# exp21dc.net
KiCad netlist of a schematic drawn in EAGLE
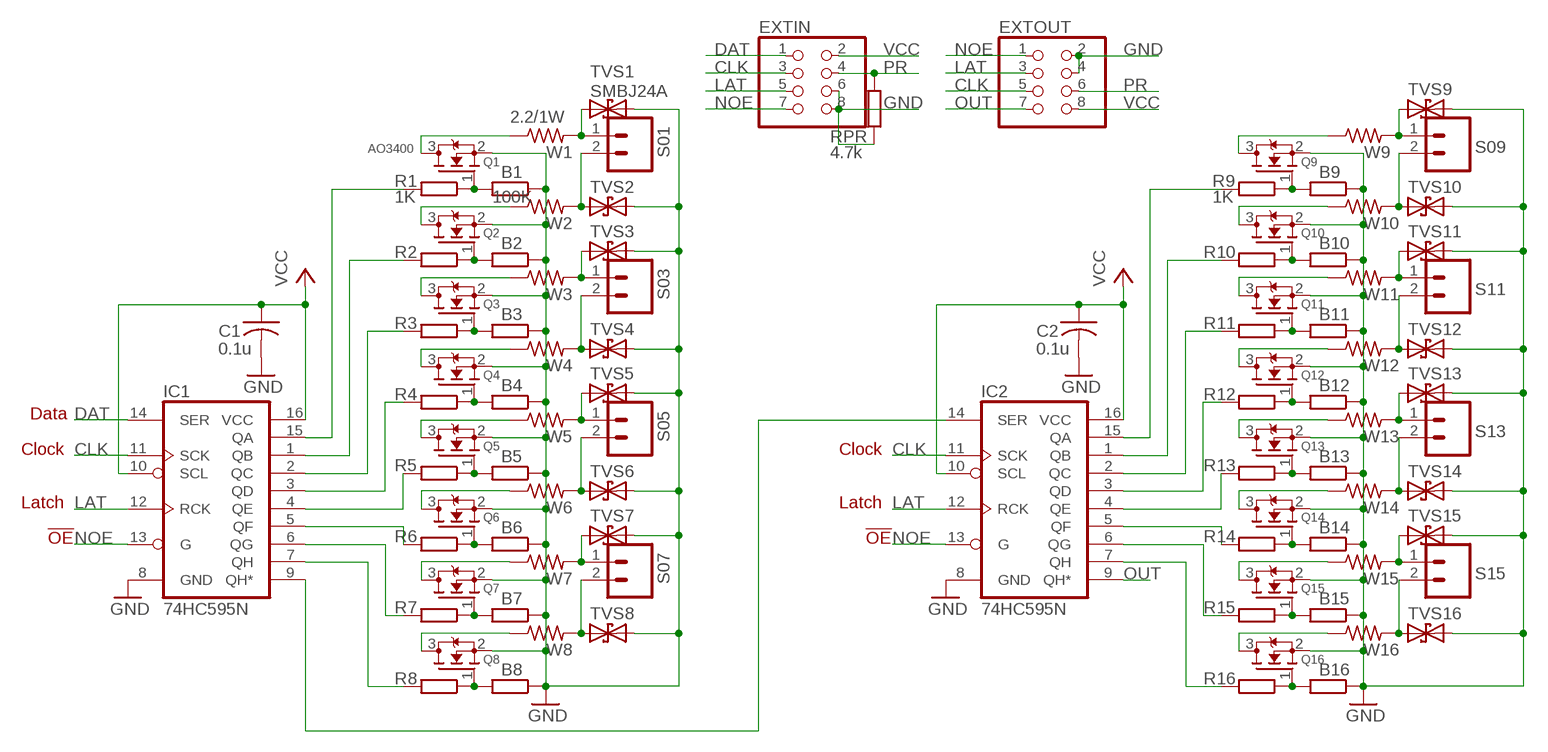
[diagram p0: schematic, sheet 1]

(export (version "E")
  (design (tool "Eeschema 10.0.6"))
  (components
    (comp (ref "B1")
      (value "100K")
      (footprint "eagle-import:R0603")
      (libsource (lib "eagle-import") (part "R-EU_R0603"))
    )
    (comp (ref "B2")
      (value "100K")
      (footprint "eagle-import:R0603")
      (libsource (lib "eagle-import") (part "R-EU_R0603"))
    )
    (comp (ref "B3")
      (value "100K")
      (footprint "eagle-import:R0603")
      (libsource (lib "eagle-import") (part "R-EU_R0603"))
    )
    (comp (ref "B4")
      (value "100K")
      (footprint "eagle-import:R0603")
      (libsource (lib "eagle-import") (part "R-EU_R0603"))
    )
    (comp (ref "B5")
      (value "100K")
      (footprint "eagle-import:R0603")
      (libsource (lib "eagle-import") (part "R-EU_R0603"))
    )
    (comp (ref "B6")
      (value "100K")
      (footprint "eagle-import:R0603")
      (libsource (lib "eagle-import") (part "R-EU_R0603"))
    )
    (comp (ref "B7")
      (value "100K")
      (footprint "eagle-import:R0603")
      (libsource (lib "eagle-import") (part "R-EU_R0603"))
    )
    (comp (ref "B8")
      (value "100K")
      (footprint "eagle-import:R0603")
      (libsource (lib "eagle-import") (part "R-EU_R0603"))
    )
    (comp (ref "B9")
      (value "100K")
      (footprint "eagle-import:R0603")
      (libsource (lib "eagle-import") (part "R-EU_R0603"))
    )
    (comp (ref "B10")
      (value "100K")
      (footprint "eagle-import:R0603")
      (libsource (lib "eagle-import") (part "R-EU_R0603"))
    )
    (comp (ref "B11")
      (value "100K")
      (footprint "eagle-import:R0603")
      (libsource (lib "eagle-import") (part "R-EU_R0603"))
    )
    (comp (ref "B12")
      (value "100K")
      (footprint "eagle-import:R0603")
      (libsource (lib "eagle-import") (part "R-EU_R0603"))
    )
    (comp (ref "B13")
      (value "100K")
      (footprint "eagle-import:R0603")
      (libsource (lib "eagle-import") (part "R-EU_R0603"))
    )
    (comp (ref "B14")
      (value "100K")
      (footprint "eagle-import:R0603")
      (libsource (lib "eagle-import") (part "R-EU_R0603"))
    )
    (comp (ref "B15")
      (value "100K")
      (footprint "eagle-import:R0603")
      (libsource (lib "eagle-import") (part "R-EU_R0603"))
    )
    (comp (ref "B16")
      (value "100K")
      (footprint "eagle-import:R0603")
      (libsource (lib "eagle-import") (part "R-EU_R0603"))
    )
    (comp (ref "C1")
      (value "0.1u")
      (footprint "eagle-import:C0603K")
      (libsource (lib "eagle-import") (part "C-USC0603K"))
    )
    (comp (ref "C2")
      (value "0.1u")
      (footprint "eagle-import:C0603K")
      (libsource (lib "eagle-import") (part "C-USC0603K"))
    )
    (comp (ref "EXTIN")
      (value "PINHD-2X4/90")
      (footprint "eagle-import:2X04_90")
      (libsource (lib "eagle-import") (part "PINHD-2X4/90"))
    )
    (comp (ref "EXTOUT")
      (value "PINHD-2X4/90")
      (footprint "eagle-import:2X04_90")
      (libsource (lib "eagle-import") (part "PINHD-2X4/90"))
    )
    (comp (ref "IC1")
      (value "74HC595N")
      (footprint "eagle-import:SO16")
      (libsource (lib "eagle-import") (part "74595DLS"))
    )
    (comp (ref "IC2")
      (value "74HC595N")
      (footprint "eagle-import:SO16")
      (libsource (lib "eagle-import") (part "74595DLS"))
    )
    (comp (ref "Q1")
      (value "AO3400")
      (footprint "eagle-import:SOT23")
      (libsource (lib "eagle-import") (part "MOSFET-NREFLOW"))
    )
    (comp (ref "Q2")
      (value "MOSFET-NREFLOW")
      (footprint "eagle-import:SOT23")
      (libsource (lib "eagle-import") (part "MOSFET-NREFLOW"))
    )
    (comp (ref "Q3")
      (value "MOSFET-NREFLOW")
      (footprint "eagle-import:SOT23")
      (libsource (lib "eagle-import") (part "MOSFET-NREFLOW"))
    )
    (comp (ref "Q4")
      (value "MOSFET-NREFLOW")
      (footprint "eagle-import:SOT23")
      (libsource (lib "eagle-import") (part "MOSFET-NREFLOW"))
    )
    (comp (ref "Q5")
      (value "MOSFET-NREFLOW")
      (footprint "eagle-import:SOT23")
      (libsource (lib "eagle-import") (part "MOSFET-NREFLOW"))
    )
    (comp (ref "Q6")
      (value "MOSFET-NREFLOW")
      (footprint "eagle-import:SOT23")
      (libsource (lib "eagle-import") (part "MOSFET-NREFLOW"))
    )
    (comp (ref "Q7")
      (value "MOSFET-NREFLOW")
      (footprint "eagle-import:SOT23")
      (libsource (lib "eagle-import") (part "MOSFET-NREFLOW"))
    )
    (comp (ref "Q8")
      (value "MOSFET-NREFLOW")
      (footprint "eagle-import:SOT23")
      (libsource (lib "eagle-import") (part "MOSFET-NREFLOW"))
    )
    (comp (ref "Q9")
      (value "MOSFET-NREFLOW")
      (footprint "eagle-import:SOT23")
      (libsource (lib "eagle-import") (part "MOSFET-NREFLOW"))
    )
    (comp (ref "Q10")
      (value "MOSFET-NREFLOW")
      (footprint "eagle-import:SOT23")
      (libsource (lib "eagle-import") (part "MOSFET-NREFLOW"))
    )
    (comp (ref "Q11")
      (value "MOSFET-NREFLOW")
      (footprint "eagle-import:SOT23")
      (libsource (lib "eagle-import") (part "MOSFET-NREFLOW"))
    )
    (comp (ref "Q12")
      (value "MOSFET-NREFLOW")
      (footprint "eagle-import:SOT23")
      (libsource (lib "eagle-import") (part "MOSFET-NREFLOW"))
    )
    (comp (ref "Q13")
      (value "MOSFET-NREFLOW")
      (footprint "eagle-import:SOT23")
      (libsource (lib "eagle-import") (part "MOSFET-NREFLOW"))
    )
    (comp (ref "Q14")
      (value "MOSFET-NREFLOW")
      (footprint "eagle-import:SOT23")
      (libsource (lib "eagle-import") (part "MOSFET-NREFLOW"))
    )
    (comp (ref "Q15")
      (value "MOSFET-NREFLOW")
      (footprint "eagle-import:SOT23")
      (libsource (lib "eagle-import") (part "MOSFET-NREFLOW"))
    )
    (comp (ref "Q16")
      (value "MOSFET-NREFLOW")
      (footprint "eagle-import:SOT23")
      (libsource (lib "eagle-import") (part "MOSFET-NREFLOW"))
    )
    (comp (ref "R1")
      (value "1K")
      (footprint "eagle-import:R0603")
      (libsource (lib "eagle-import") (part "R-EU_R0603"))
    )
    (comp (ref "R2")
      (value "1K")
      (footprint "eagle-import:R0603")
      (libsource (lib "eagle-import") (part "R-EU_R0603"))
    )
    (comp (ref "R3")
      (value "1K")
      (footprint "eagle-import:R0603")
      (libsource (lib "eagle-import") (part "R-EU_R0603"))
    )
    (comp (ref "R4")
      (value "1K")
      (footprint "eagle-import:R0603")
      (libsource (lib "eagle-import") (part "R-EU_R0603"))
    )
    (comp (ref "R5")
      (value "1K")
      (footprint "eagle-import:R0603")
      (libsource (lib "eagle-import") (part "R-EU_R0603"))
    )
    (comp (ref "R6")
      (value "1K")
      (footprint "eagle-import:R0603")
      (libsource (lib "eagle-import") (part "R-EU_R0603"))
    )
    (comp (ref "R7")
      (value "1K")
      (footprint "eagle-import:R0603")
      (libsource (lib "eagle-import") (part "R-EU_R0603"))
    )
    (comp (ref "R8")
      (value "1K")
      (footprint "eagle-import:R0603")
      (libsource (lib "eagle-import") (part "R-EU_R0603"))
    )
    (comp (ref "R9")
      (value "1K")
      (footprint "eagle-import:R0603")
      (libsource (lib "eagle-import") (part "R-EU_R0603"))
    )
    (comp (ref "R10")
      (value "1K")
      (footprint "eagle-import:R0603")
      (libsource (lib "eagle-import") (part "R-EU_R0603"))
    )
    (comp (ref "R11")
      (value "1K")
      (footprint "eagle-import:R0603")
      (libsource (lib "eagle-import") (part "R-EU_R0603"))
    )
    (comp (ref "R12")
      (value "1K")
      (footprint "eagle-import:R0603")
      (libsource (lib "eagle-import") (part "R-EU_R0603"))
    )
    (comp (ref "R13")
      (value "1K")
      (footprint "eagle-import:R0603")
      (libsource (lib "eagle-import") (part "R-EU_R0603"))
    )
    (comp (ref "R14")
      (value "1K")
      (footprint "eagle-import:R0603")
      (libsource (lib "eagle-import") (part "R-EU_R0603"))
    )
    (comp (ref "R15")
      (value "1K")
      (footprint "eagle-import:R0603")
      (libsource (lib "eagle-import") (part "R-EU_R0603"))
    )
    (comp (ref "R16")
      (value "1K")
      (footprint "eagle-import:R0603")
      (libsource (lib "eagle-import") (part "R-EU_R0603"))
    )
    (comp (ref "RPR")
      (value "4.7k")
      (footprint "eagle-import:R0603")
      (libsource (lib "eagle-import") (part "R-EU_R0603"))
    )
    (comp (ref "S01")
      (value "M025MM-X")
      (footprint "eagle-import:SCREWTERMINAL-5MM-2-X")
      (libsource (lib "eagle-import") (part "M025MM-X"))
    )
    (comp (ref "S03")
      (value "M025MM-X")
      (footprint "eagle-import:SCREWTERMINAL-5MM-2-X")
      (libsource (lib "eagle-import") (part "M025MM-X"))
    )
    (comp (ref "S05")
      (value "M025MM-X")
      (footprint "eagle-import:SCREWTERMINAL-5MM-2-X")
      (libsource (lib "eagle-import") (part "M025MM-X"))
    )
    (comp (ref "S07")
      (value "M025MM-X")
      (footprint "eagle-import:SCREWTERMINAL-5MM-2-X")
      (libsource (lib "eagle-import") (part "M025MM-X"))
    )
    (comp (ref "S09")
      (value "M025MM-X")
      (footprint "eagle-import:SCREWTERMINAL-5MM-2-X")
      (libsource (lib "eagle-import") (part "M025MM-X"))
    )
    (comp (ref "S11")
      (value "M025MM-X")
      (footprint "eagle-import:SCREWTERMINAL-5MM-2-X")
      (libsource (lib "eagle-import") (part "M025MM-X"))
    )
    (comp (ref "S13")
      (value "M025MM-X")
      (footprint "eagle-import:SCREWTERMINAL-5MM-2-X")
      (libsource (lib "eagle-import") (part "M025MM-X"))
    )
    (comp (ref "S15")
      (value "M025MM-X")
      (footprint "eagle-import:SCREWTERMINAL-5MM-2-X")
      (libsource (lib "eagle-import") (part "M025MM-X"))
    )
    (comp (ref "TVS1")
      (value "SMBJ24A")
      (footprint "eagle-import:SMB")
      (libsource (lib "eagle-import") (part "TVSSMB"))
    )
    (comp (ref "TVS2")
      (value "TVSSMB")
      (footprint "eagle-import:SMB")
      (libsource (lib "eagle-import") (part "TVSSMB"))
    )
    (comp (ref "TVS3")
      (value "TVSSMB")
      (footprint "eagle-import:SMB")
      (libsource (lib "eagle-import") (part "TVSSMB"))
    )
    (comp (ref "TVS4")
      (value "TVSSMB")
      (footprint "eagle-import:SMB")
      (libsource (lib "eagle-import") (part "TVSSMB"))
    )
    (comp (ref "TVS5")
      (value "TVSSMB")
      (footprint "eagle-import:SMB")
      (libsource (lib "eagle-import") (part "TVSSMB"))
    )
    (comp (ref "TVS6")
      (value "TVSSMB")
      (footprint "eagle-import:SMB")
      (libsource (lib "eagle-import") (part "TVSSMB"))
    )
    (comp (ref "TVS7")
      (value "TVSSMB")
      (footprint "eagle-import:SMB")
      (libsource (lib "eagle-import") (part "TVSSMB"))
    )
    (comp (ref "TVS8")
      (value "TVSSMB")
      (footprint "eagle-import:SMB")
      (libsource (lib "eagle-import") (part "TVSSMB"))
    )
    (comp (ref "TVS9")
      (value "TVSSMB")
      (footprint "eagle-import:SMB")
      (libsource (lib "eagle-import") (part "TVSSMB"))
    )
    (comp (ref "TVS10")
      (value "TVSSMB")
      (footprint "eagle-import:SMB")
      (libsource (lib "eagle-import") (part "TVSSMB"))
    )
    (comp (ref "TVS11")
      (value "TVSSMB")
      (footprint "eagle-import:SMB")
      (libsource (lib "eagle-import") (part "TVSSMB"))
    )
    (comp (ref "TVS12")
      (value "TVSSMB")
      (footprint "eagle-import:SMB")
      (libsource (lib "eagle-import") (part "TVSSMB"))
    )
    (comp (ref "TVS13")
      (value "TVSSMB")
      (footprint "eagle-import:SMB")
      (libsource (lib "eagle-import") (part "TVSSMB"))
    )
    (comp (ref "TVS14")
      (value "TVSSMB")
      (footprint "eagle-import:SMB")
      (libsource (lib "eagle-import") (part "TVSSMB"))
    )
    (comp (ref "TVS15")
      (value "TVSSMB")
      (footprint "eagle-import:SMB")
      (libsource (lib "eagle-import") (part "TVSSMB"))
    )
    (comp (ref "TVS16")
      (value "TVSSMB")
      (footprint "eagle-import:SMB")
      (libsource (lib "eagle-import") (part "TVSSMB"))
    )
    (comp (ref "W1")
      (value "2.2/1W")
      (footprint "eagle-import:R2512")
      (libsource (lib "eagle-import") (part "R-US_R2512"))
    )
    (comp (ref "W2")
      (value "R-US_R2512")
      (footprint "eagle-import:R2512")
      (libsource (lib "eagle-import") (part "R-US_R2512"))
    )
    (comp (ref "W3")
      (value "R-US_R2512")
      (footprint "eagle-import:R2512")
      (libsource (lib "eagle-import") (part "R-US_R2512"))
    )
    (comp (ref "W4")
      (value "R-US_R2512")
      (footprint "eagle-import:R2512")
      (libsource (lib "eagle-import") (part "R-US_R2512"))
    )
    (comp (ref "W5")
      (value "R-US_R2512")
      (footprint "eagle-import:R2512")
      (libsource (lib "eagle-import") (part "R-US_R2512"))
    )
    (comp (ref "W6")
      (value "R-US_R2512")
      (footprint "eagle-import:R2512")
      (libsource (lib "eagle-import") (part "R-US_R2512"))
    )
    (comp (ref "W7")
      (value "R-US_R2512")
      (footprint "eagle-import:R2512")
      (libsource (lib "eagle-import") (part "R-US_R2512"))
    )
    (comp (ref "W8")
      (value "R-US_R2512")
      (footprint "eagle-import:R2512")
      (libsource (lib "eagle-import") (part "R-US_R2512"))
    )
    (comp (ref "W9")
      (value "R-US_R2512")
      (footprint "eagle-import:R2512")
      (libsource (lib "eagle-import") (part "R-US_R2512"))
    )
    (comp (ref "W10")
      (value "R-US_R2512")
      (footprint "eagle-import:R2512")
      (libsource (lib "eagle-import") (part "R-US_R2512"))
    )
    (comp (ref "W11")
      (value "R-US_R2512")
      (footprint "eagle-import:R2512")
      (libsource (lib "eagle-import") (part "R-US_R2512"))
    )
    (comp (ref "W12")
      (value "R-US_R2512")
      (footprint "eagle-import:R2512")
      (libsource (lib "eagle-import") (part "R-US_R2512"))
    )
    (comp (ref "W13")
      (value "R-US_R2512")
      (footprint "eagle-import:R2512")
      (libsource (lib "eagle-import") (part "R-US_R2512"))
    )
    (comp (ref "W14")
      (value "R-US_R2512")
      (footprint "eagle-import:R2512")
      (libsource (lib "eagle-import") (part "R-US_R2512"))
    )
    (comp (ref "W15")
      (value "R-US_R2512")
      (footprint "eagle-import:R2512")
      (libsource (lib "eagle-import") (part "R-US_R2512"))
    )
    (comp (ref "W16")
      (value "R-US_R2512")
      (footprint "eagle-import:R2512")
      (libsource (lib "eagle-import") (part "R-US_R2512"))
    )
  )
  (nets
    (net (code "1") (name "/CLK") (class "Default")
      (node (ref "EXTIN") (pin "3") (pinfunction "3_3") (pintype "passive"))
      (node (ref "EXTOUT") (pin "5") (pinfunction "5_5") (pintype "passive"))
      (node (ref "IC1") (pin "11") (pinfunction "SCK_11") (pintype "input"))
      (node (ref "IC2") (pin "11") (pinfunction "SCK_11") (pintype "input"))
    )
    (net (code "2") (name "/DAT") (class "Default")
      (node (ref "EXTIN") (pin "1") (pinfunction "1_1") (pintype "passive"))
      (node (ref "IC1") (pin "14") (pinfunction "SER_14") (pintype "input"))
    )
    (net (code "3") (name "/LAT") (class "Default")
      (node (ref "EXTIN") (pin "5") (pinfunction "5_5") (pintype "passive"))
      (node (ref "EXTOUT") (pin "3") (pinfunction "3_3") (pintype "passive"))
      (node (ref "IC1") (pin "12") (pinfunction "RCK_12") (pintype "input"))
      (node (ref "IC2") (pin "12") (pinfunction "RCK_12") (pintype "input"))
    )
    (net (code "4") (name "/NOE") (class "Default")
      (node (ref "EXTIN") (pin "7") (pinfunction "7_7") (pintype "passive"))
      (node (ref "EXTOUT") (pin "1") (pinfunction "1_1") (pintype "passive"))
      (node (ref "IC1") (pin "13") (pinfunction "G_13") (pintype "input"))
      (node (ref "IC2") (pin "13") (pinfunction "G_13") (pintype "input"))
    )
    (net (code "5") (name "/OUT") (class "Default")
      (node (ref "EXTOUT") (pin "7") (pinfunction "7_7") (pintype "passive"))
      (node (ref "IC2") (pin "9") (pinfunction "QH*_9") (pintype "tri_state"))
    )
    (net (code "6") (name "/PR") (class "Default")
      (node (ref "EXTIN") (pin "4") (pinfunction "4_4") (pintype "passive"))
      (node (ref "EXTOUT") (pin "6") (pinfunction "6_6") (pintype "passive"))
      (node (ref "RPR") (pin "2") (pinfunction "2_2") (pintype "passive"))
    )
    (net (code "7") (name "GND") (class "Default")
      (node (ref "B1") (pin "1") (pinfunction "1_1") (pintype "passive"))
      (node (ref "B10") (pin "1") (pinfunction "1_1") (pintype "passive"))
      (node (ref "B11") (pin "1") (pinfunction "1_1") (pintype "passive"))
      (node (ref "B12") (pin "1") (pinfunction "1_1") (pintype "passive"))
      (node (ref "B13") (pin "1") (pinfunction "1_1") (pintype "passive"))
      (node (ref "B14") (pin "1") (pinfunction "1_1") (pintype "passive"))
      (node (ref "B15") (pin "1") (pinfunction "1_1") (pintype "passive"))
      (node (ref "B16") (pin "1") (pinfunction "1_1") (pintype "passive"))
      (node (ref "B2") (pin "1") (pinfunction "1_1") (pintype "passive"))
      (node (ref "B3") (pin "1") (pinfunction "1_1") (pintype "passive"))
      (node (ref "B4") (pin "1") (pinfunction "1_1") (pintype "passive"))
      (node (ref "B5") (pin "1") (pinfunction "1_1") (pintype "passive"))
      (node (ref "B6") (pin "1") (pinfunction "1_1") (pintype "passive"))
      (node (ref "B7") (pin "1") (pinfunction "1_1") (pintype "passive"))
      (node (ref "B8") (pin "1") (pinfunction "1_1") (pintype "passive"))
      (node (ref "B9") (pin "1") (pinfunction "1_1") (pintype "passive"))
      (node (ref "C1") (pin "2") (pinfunction "2_2") (pintype "passive"))
      (node (ref "C2") (pin "2") (pinfunction "2_2") (pintype "passive"))
      (node (ref "EXTIN") (pin "6") (pinfunction "6_6") (pintype "passive"))
      (node (ref "EXTIN") (pin "8") (pinfunction "8_8") (pintype "passive"))
      (node (ref "EXTOUT") (pin "2") (pinfunction "2_2") (pintype "passive"))
      (node (ref "EXTOUT") (pin "4") (pinfunction "4_4") (pintype "passive"))
      (node (ref "IC1") (pin "8") (pinfunction "GND_8") (pintype "power_in"))
      (node (ref "IC2") (pin "8") (pinfunction "GND_8") (pintype "power_in"))
      (node (ref "Q1") (pin "2") (pinfunction "S_2") (pintype "bidirectional"))
      (node (ref "Q10") (pin "2") (pinfunction "S_2") (pintype "bidirectional"))
      (node (ref "Q11") (pin "2") (pinfunction "S_2") (pintype "bidirectional"))
      (node (ref "Q12") (pin "2") (pinfunction "S_2") (pintype "bidirectional"))
      (node (ref "Q13") (pin "2") (pinfunction "S_2") (pintype "bidirectional"))
      (node (ref "Q14") (pin "2") (pinfunction "S_2") (pintype "bidirectional"))
      (node (ref "Q15") (pin "2") (pinfunction "S_2") (pintype "bidirectional"))
      (node (ref "Q16") (pin "2") (pinfunction "S_2") (pintype "bidirectional"))
      (node (ref "Q2") (pin "2") (pinfunction "S_2") (pintype "bidirectional"))
      (node (ref "Q3") (pin "2") (pinfunction "S_2") (pintype "bidirectional"))
      (node (ref "Q4") (pin "2") (pinfunction "S_2") (pintype "bidirectional"))
      (node (ref "Q5") (pin "2") (pinfunction "S_2") (pintype "bidirectional"))
      (node (ref "Q6") (pin "2") (pinfunction "S_2") (pintype "bidirectional"))
      (node (ref "Q7") (pin "2") (pinfunction "S_2") (pintype "bidirectional"))
      (node (ref "Q8") (pin "2") (pinfunction "S_2") (pintype "bidirectional"))
      (node (ref "Q9") (pin "2") (pinfunction "S_2") (pintype "bidirectional"))
      (node (ref "RPR") (pin "1") (pinfunction "1_1") (pintype "passive"))
      (node (ref "TVS1") (pin "C") (pinfunction "2_C") (pintype "passive"))
      (node (ref "TVS10") (pin "C") (pinfunction "2_C") (pintype "passive"))
      (node (ref "TVS11") (pin "C") (pinfunction "2_C") (pintype "passive"))
      (node (ref "TVS12") (pin "C") (pinfunction "2_C") (pintype "passive"))
      (node (ref "TVS13") (pin "C") (pinfunction "2_C") (pintype "passive"))
      (node (ref "TVS14") (pin "C") (pinfunction "2_C") (pintype "passive"))
      (node (ref "TVS15") (pin "C") (pinfunction "2_C") (pintype "passive"))
      (node (ref "TVS16") (pin "C") (pinfunction "2_C") (pintype "passive"))
      (node (ref "TVS2") (pin "C") (pinfunction "2_C") (pintype "passive"))
      (node (ref "TVS3") (pin "C") (pinfunction "2_C") (pintype "passive"))
      (node (ref "TVS4") (pin "C") (pinfunction "2_C") (pintype "passive"))
      (node (ref "TVS5") (pin "C") (pinfunction "2_C") (pintype "passive"))
      (node (ref "TVS6") (pin "C") (pinfunction "2_C") (pintype "passive"))
      (node (ref "TVS7") (pin "C") (pinfunction "2_C") (pintype "passive"))
      (node (ref "TVS8") (pin "C") (pinfunction "2_C") (pintype "passive"))
      (node (ref "TVS9") (pin "C") (pinfunction "2_C") (pintype "passive"))
    )
    (net (code "8") (name "Net-(IC1-QA)") (class "Default")
      (node (ref "IC1") (pin "15") (pinfunction "QA_15") (pintype "tri_state"))
      (node (ref "R1") (pin "2") (pinfunction "2_2") (pintype "passive"))
    )
    (net (code "9") (name "Net-(IC1-QB)") (class "Default")
      (node (ref "IC1") (pin "1") (pinfunction "QB_1") (pintype "tri_state"))
      (node (ref "R2") (pin "2") (pinfunction "2_2") (pintype "passive"))
    )
    (net (code "10") (name "Net-(IC1-QC)") (class "Default")
      (node (ref "IC1") (pin "2") (pinfunction "QC_2") (pintype "tri_state"))
      (node (ref "R3") (pin "2") (pinfunction "2_2") (pintype "passive"))
    )
    (net (code "11") (name "Net-(IC1-QD)") (class "Default")
      (node (ref "IC1") (pin "3") (pinfunction "QD_3") (pintype "tri_state"))
      (node (ref "R4") (pin "2") (pinfunction "2_2") (pintype "passive"))
    )
    (net (code "12") (name "Net-(IC1-QE)") (class "Default")
      (node (ref "IC1") (pin "4") (pinfunction "QE_4") (pintype "tri_state"))
      (node (ref "R5") (pin "2") (pinfunction "2_2") (pintype "passive"))
    )
    (net (code "13") (name "Net-(IC1-QF)") (class "Default")
      (node (ref "IC1") (pin "5") (pinfunction "QF_5") (pintype "tri_state"))
      (node (ref "R6") (pin "2") (pinfunction "2_2") (pintype "passive"))
    )
    (net (code "14") (name "Net-(IC1-QG)") (class "Default")
      (node (ref "IC1") (pin "6") (pinfunction "QG_6") (pintype "tri_state"))
      (node (ref "R7") (pin "2") (pinfunction "2_2") (pintype "passive"))
    )
    (net (code "15") (name "Net-(IC1-QH)") (class "Default")
      (node (ref "IC1") (pin "7") (pinfunction "QH_7") (pintype "tri_state"))
      (node (ref "R8") (pin "2") (pinfunction "2_2") (pintype "passive"))
    )
    (net (code "16") (name "Net-(IC1-QH*)") (class "Default")
      (node (ref "IC1") (pin "9") (pinfunction "QH*_9") (pintype "tri_state"))
      (node (ref "IC2") (pin "14") (pinfunction "SER_14") (pintype "input"))
    )
    (net (code "17") (name "Net-(IC2-QA)") (class "Default")
      (node (ref "IC2") (pin "15") (pinfunction "QA_15") (pintype "tri_state"))
      (node (ref "R9") (pin "2") (pinfunction "2_2") (pintype "passive"))
    )
    (net (code "18") (name "Net-(IC2-QB)") (class "Default")
      (node (ref "IC2") (pin "1") (pinfunction "QB_1") (pintype "tri_state"))
      (node (ref "R10") (pin "2") (pinfunction "2_2") (pintype "passive"))
    )
    (net (code "19") (name "Net-(IC2-QC)") (class "Default")
      (node (ref "IC2") (pin "2") (pinfunction "QC_2") (pintype "tri_state"))
      (node (ref "R11") (pin "2") (pinfunction "2_2") (pintype "passive"))
    )
    (net (code "20") (name "Net-(IC2-QD)") (class "Default")
      (node (ref "IC2") (pin "3") (pinfunction "QD_3") (pintype "tri_state"))
      (node (ref "R12") (pin "2") (pinfunction "2_2") (pintype "passive"))
    )
    (net (code "21") (name "Net-(IC2-QE)") (class "Default")
      (node (ref "IC2") (pin "4") (pinfunction "QE_4") (pintype "tri_state"))
      (node (ref "R13") (pin "2") (pinfunction "2_2") (pintype "passive"))
    )
    (net (code "22") (name "Net-(IC2-QF)") (class "Default")
      (node (ref "IC2") (pin "5") (pinfunction "QF_5") (pintype "tri_state"))
      (node (ref "R14") (pin "2") (pinfunction "2_2") (pintype "passive"))
    )
    (net (code "23") (name "Net-(IC2-QG)") (class "Default")
      (node (ref "IC2") (pin "6") (pinfunction "QG_6") (pintype "tri_state"))
      (node (ref "R15") (pin "2") (pinfunction "2_2") (pintype "passive"))
    )
    (net (code "24") (name "Net-(IC2-QH)") (class "Default")
      (node (ref "IC2") (pin "7") (pinfunction "QH_7") (pintype "tri_state"))
      (node (ref "R16") (pin "2") (pinfunction "2_2") (pintype "passive"))
    )
    (net (code "25") (name "Net-(Q1-D)") (class "Default")
      (node (ref "Q1") (pin "3") (pinfunction "D_3") (pintype "bidirectional"))
      (node (ref "W1") (pin "1") (pinfunction "1_1") (pintype "passive"))
    )
    (net (code "26") (name "Net-(Q1-G)") (class "Default")
      (node (ref "B1") (pin "2") (pinfunction "2_2") (pintype "passive"))
      (node (ref "Q1") (pin "1") (pinfunction "G_1") (pintype "bidirectional"))
      (node (ref "R1") (pin "1") (pinfunction "1_1") (pintype "passive"))
    )
    (net (code "27") (name "Net-(Q2-D)") (class "Default")
      (node (ref "Q2") (pin "3") (pinfunction "D_3") (pintype "bidirectional"))
      (node (ref "W2") (pin "1") (pinfunction "1_1") (pintype "passive"))
    )
    (net (code "28") (name "Net-(Q2-G)") (class "Default")
      (node (ref "B2") (pin "2") (pinfunction "2_2") (pintype "passive"))
      (node (ref "Q2") (pin "1") (pinfunction "G_1") (pintype "bidirectional"))
      (node (ref "R2") (pin "1") (pinfunction "1_1") (pintype "passive"))
    )
    (net (code "29") (name "Net-(Q3-D)") (class "Default")
      (node (ref "Q3") (pin "3") (pinfunction "D_3") (pintype "bidirectional"))
      (node (ref "W3") (pin "1") (pinfunction "1_1") (pintype "passive"))
    )
    (net (code "30") (name "Net-(Q3-G)") (class "Default")
      (node (ref "B3") (pin "2") (pinfunction "2_2") (pintype "passive"))
      (node (ref "Q3") (pin "1") (pinfunction "G_1") (pintype "bidirectional"))
      (node (ref "R3") (pin "1") (pinfunction "1_1") (pintype "passive"))
    )
    (net (code "31") (name "Net-(Q4-D)") (class "Default")
      (node (ref "Q4") (pin "3") (pinfunction "D_3") (pintype "bidirectional"))
      (node (ref "W4") (pin "1") (pinfunction "1_1") (pintype "passive"))
    )
    (net (code "32") (name "Net-(Q4-G)") (class "Default")
      (node (ref "B4") (pin "2") (pinfunction "2_2") (pintype "passive"))
      (node (ref "Q4") (pin "1") (pinfunction "G_1") (pintype "bidirectional"))
      (node (ref "R4") (pin "1") (pinfunction "1_1") (pintype "passive"))
    )
    (net (code "33") (name "Net-(Q5-D)") (class "Default")
      (node (ref "Q5") (pin "3") (pinfunction "D_3") (pintype "bidirectional"))
      (node (ref "W5") (pin "1") (pinfunction "1_1") (pintype "passive"))
    )
    (net (code "34") (name "Net-(Q5-G)") (class "Default")
      (node (ref "B5") (pin "2") (pinfunction "2_2") (pintype "passive"))
      (node (ref "Q5") (pin "1") (pinfunction "G_1") (pintype "bidirectional"))
      (node (ref "R5") (pin "1") (pinfunction "1_1") (pintype "passive"))
    )
    (net (code "35") (name "Net-(Q6-D)") (class "Default")
      (node (ref "Q6") (pin "3") (pinfunction "D_3") (pintype "bidirectional"))
      (node (ref "W6") (pin "1") (pinfunction "1_1") (pintype "passive"))
    )
    (net (code "36") (name "Net-(Q6-G)") (class "Default")
      (node (ref "B6") (pin "2") (pinfunction "2_2") (pintype "passive"))
      (node (ref "Q6") (pin "1") (pinfunction "G_1") (pintype "bidirectional"))
      (node (ref "R6") (pin "1") (pinfunction "1_1") (pintype "passive"))
    )
    (net (code "37") (name "Net-(Q7-D)") (class "Default")
      (node (ref "Q7") (pin "3") (pinfunction "D_3") (pintype "bidirectional"))
      (node (ref "W7") (pin "1") (pinfunction "1_1") (pintype "passive"))
    )
    (net (code "38") (name "Net-(Q7-G)") (class "Default")
      (node (ref "B7") (pin "2") (pinfunction "2_2") (pintype "passive"))
      (node (ref "Q7") (pin "1") (pinfunction "G_1") (pintype "bidirectional"))
      (node (ref "R7") (pin "1") (pinfunction "1_1") (pintype "passive"))
    )
    (net (code "39") (name "Net-(Q8-D)") (class "Default")
      (node (ref "Q8") (pin "3") (pinfunction "D_3") (pintype "bidirectional"))
      (node (ref "W8") (pin "1") (pinfunction "1_1") (pintype "passive"))
    )
    (net (code "40") (name "Net-(Q8-G)") (class "Default")
      (node (ref "B8") (pin "2") (pinfunction "2_2") (pintype "passive"))
      (node (ref "Q8") (pin "1") (pinfunction "G_1") (pintype "bidirectional"))
      (node (ref "R8") (pin "1") (pinfunction "1_1") (pintype "passive"))
    )
    (net (code "41") (name "Net-(Q9-D)") (class "Default")
      (node (ref "Q9") (pin "3") (pinfunction "D_3") (pintype "bidirectional"))
      (node (ref "W9") (pin "1") (pinfunction "1_1") (pintype "passive"))
    )
    (net (code "42") (name "Net-(Q9-G)") (class "Default")
      (node (ref "B9") (pin "2") (pinfunction "2_2") (pintype "passive"))
      (node (ref "Q9") (pin "1") (pinfunction "G_1") (pintype "bidirectional"))
      (node (ref "R9") (pin "1") (pinfunction "1_1") (pintype "passive"))
    )
    (net (code "43") (name "Net-(Q10-D)") (class "Default")
      (node (ref "Q10") (pin "3") (pinfunction "D_3") (pintype "bidirectional"))
      (node (ref "W10") (pin "1") (pinfunction "1_1") (pintype "passive"))
    )
    (net (code "44") (name "Net-(Q10-G)") (class "Default")
      (node (ref "B10") (pin "2") (pinfunction "2_2") (pintype "passive"))
      (node (ref "Q10") (pin "1") (pinfunction "G_1") (pintype "bidirectional"))
      (node (ref "R10") (pin "1") (pinfunction "1_1") (pintype "passive"))
    )
    (net (code "45") (name "Net-(Q11-D)") (class "Default")
      (node (ref "Q11") (pin "3") (pinfunction "D_3") (pintype "bidirectional"))
      (node (ref "W11") (pin "1") (pinfunction "1_1") (pintype "passive"))
    )
    (net (code "46") (name "Net-(Q11-G)") (class "Default")
      (node (ref "B11") (pin "2") (pinfunction "2_2") (pintype "passive"))
      (node (ref "Q11") (pin "1") (pinfunction "G_1") (pintype "bidirectional"))
      (node (ref "R11") (pin "1") (pinfunction "1_1") (pintype "passive"))
    )
    (net (code "47") (name "Net-(Q12-D)") (class "Default")
      (node (ref "Q12") (pin "3") (pinfunction "D_3") (pintype "bidirectional"))
      (node (ref "W12") (pin "1") (pinfunction "1_1") (pintype "passive"))
    )
    (net (code "48") (name "Net-(Q12-G)") (class "Default")
      (node (ref "B12") (pin "2") (pinfunction "2_2") (pintype "passive"))
      (node (ref "Q12") (pin "1") (pinfunction "G_1") (pintype "bidirectional"))
      (node (ref "R12") (pin "1") (pinfunction "1_1") (pintype "passive"))
    )
    (net (code "49") (name "Net-(Q13-D)") (class "Default")
      (node (ref "Q13") (pin "3") (pinfunction "D_3") (pintype "bidirectional"))
      (node (ref "W13") (pin "1") (pinfunction "1_1") (pintype "passive"))
    )
    (net (code "50") (name "Net-(Q13-G)") (class "Default")
      (node (ref "B13") (pin "2") (pinfunction "2_2") (pintype "passive"))
      (node (ref "Q13") (pin "1") (pinfunction "G_1") (pintype "bidirectional"))
      (node (ref "R13") (pin "1") (pinfunction "1_1") (pintype "passive"))
    )
    (net (code "51") (name "Net-(Q14-D)") (class "Default")
      (node (ref "Q14") (pin "3") (pinfunction "D_3") (pintype "bidirectional"))
      (node (ref "W14") (pin "1") (pinfunction "1_1") (pintype "passive"))
    )
    (net (code "52") (name "Net-(Q14-G)") (class "Default")
      (node (ref "B14") (pin "2") (pinfunction "2_2") (pintype "passive"))
      (node (ref "Q14") (pin "1") (pinfunction "G_1") (pintype "bidirectional"))
      (node (ref "R14") (pin "1") (pinfunction "1_1") (pintype "passive"))
    )
    (net (code "53") (name "Net-(Q15-D)") (class "Default")
      (node (ref "Q15") (pin "3") (pinfunction "D_3") (pintype "bidirectional"))
      (node (ref "W15") (pin "1") (pinfunction "1_1") (pintype "passive"))
    )
    (net (code "54") (name "Net-(Q15-G)") (class "Default")
      (node (ref "B15") (pin "2") (pinfunction "2_2") (pintype "passive"))
      (node (ref "Q15") (pin "1") (pinfunction "G_1") (pintype "bidirectional"))
      (node (ref "R15") (pin "1") (pinfunction "1_1") (pintype "passive"))
    )
    (net (code "55") (name "Net-(Q16-D)") (class "Default")
      (node (ref "Q16") (pin "3") (pinfunction "D_3") (pintype "bidirectional"))
      (node (ref "W16") (pin "1") (pinfunction "1_1") (pintype "passive"))
    )
    (net (code "56") (name "Net-(Q16-G)") (class "Default")
      (node (ref "B16") (pin "2") (pinfunction "2_2") (pintype "passive"))
      (node (ref "Q16") (pin "1") (pinfunction "G_1") (pintype "bidirectional"))
      (node (ref "R16") (pin "1") (pinfunction "1_1") (pintype "passive"))
    )
    (net (code "57") (name "Net-(TVS1-1)") (class "Default")
      (node (ref "S01") (pin "1") (pinfunction "1_1") (pintype "passive"))
      (node (ref "TVS1") (pin "A") (pinfunction "1_A") (pintype "passive"))
      (node (ref "W1") (pin "2") (pinfunction "2_2") (pintype "passive"))
    )
    (net (code "58") (name "Net-(TVS2-1)") (class "Default")
      (node (ref "S01") (pin "2") (pinfunction "2_2") (pintype "passive"))
      (node (ref "TVS2") (pin "A") (pinfunction "1_A") (pintype "passive"))
      (node (ref "W2") (pin "2") (pinfunction "2_2") (pintype "passive"))
    )
    (net (code "59") (name "Net-(TVS3-1)") (class "Default")
      (node (ref "S03") (pin "1") (pinfunction "1_1") (pintype "passive"))
      (node (ref "TVS3") (pin "A") (pinfunction "1_A") (pintype "passive"))
      (node (ref "W3") (pin "2") (pinfunction "2_2") (pintype "passive"))
    )
    (net (code "60") (name "Net-(TVS4-1)") (class "Default")
      (node (ref "S03") (pin "2") (pinfunction "2_2") (pintype "passive"))
      (node (ref "TVS4") (pin "A") (pinfunction "1_A") (pintype "passive"))
      (node (ref "W4") (pin "2") (pinfunction "2_2") (pintype "passive"))
    )
    (net (code "61") (name "Net-(TVS5-1)") (class "Default")
      (node (ref "S05") (pin "1") (pinfunction "1_1") (pintype "passive"))
      (node (ref "TVS5") (pin "A") (pinfunction "1_A") (pintype "passive"))
      (node (ref "W5") (pin "2") (pinfunction "2_2") (pintype "passive"))
    )
    (net (code "62") (name "Net-(TVS6-1)") (class "Default")
      (node (ref "S05") (pin "2") (pinfunction "2_2") (pintype "passive"))
      (node (ref "TVS6") (pin "A") (pinfunction "1_A") (pintype "passive"))
      (node (ref "W6") (pin "2") (pinfunction "2_2") (pintype "passive"))
    )
    (net (code "63") (name "Net-(TVS7-1)") (class "Default")
      (node (ref "S07") (pin "1") (pinfunction "1_1") (pintype "passive"))
      (node (ref "TVS7") (pin "A") (pinfunction "1_A") (pintype "passive"))
      (node (ref "W7") (pin "2") (pinfunction "2_2") (pintype "passive"))
    )
    (net (code "64") (name "Net-(TVS8-1)") (class "Default")
      (node (ref "S07") (pin "2") (pinfunction "2_2") (pintype "passive"))
      (node (ref "TVS8") (pin "A") (pinfunction "1_A") (pintype "passive"))
      (node (ref "W8") (pin "2") (pinfunction "2_2") (pintype "passive"))
    )
    (net (code "65") (name "Net-(TVS9-1)") (class "Default")
      (node (ref "S09") (pin "1") (pinfunction "1_1") (pintype "passive"))
      (node (ref "TVS9") (pin "A") (pinfunction "1_A") (pintype "passive"))
      (node (ref "W9") (pin "2") (pinfunction "2_2") (pintype "passive"))
    )
    (net (code "66") (name "Net-(TVS10-1)") (class "Default")
      (node (ref "S09") (pin "2") (pinfunction "2_2") (pintype "passive"))
      (node (ref "TVS10") (pin "A") (pinfunction "1_A") (pintype "passive"))
      (node (ref "W10") (pin "2") (pinfunction "2_2") (pintype "passive"))
    )
    (net (code "67") (name "Net-(TVS11-1)") (class "Default")
      (node (ref "S11") (pin "1") (pinfunction "1_1") (pintype "passive"))
      (node (ref "TVS11") (pin "A") (pinfunction "1_A") (pintype "passive"))
      (node (ref "W11") (pin "2") (pinfunction "2_2") (pintype "passive"))
    )
    (net (code "68") (name "Net-(TVS12-1)") (class "Default")
      (node (ref "S11") (pin "2") (pinfunction "2_2") (pintype "passive"))
      (node (ref "TVS12") (pin "A") (pinfunction "1_A") (pintype "passive"))
      (node (ref "W12") (pin "2") (pinfunction "2_2") (pintype "passive"))
    )
    (net (code "69") (name "Net-(TVS13-1)") (class "Default")
      (node (ref "S13") (pin "1") (pinfunction "1_1") (pintype "passive"))
      (node (ref "TVS13") (pin "A") (pinfunction "1_A") (pintype "passive"))
      (node (ref "W13") (pin "2") (pinfunction "2_2") (pintype "passive"))
    )
    (net (code "70") (name "Net-(TVS14-1)") (class "Default")
      (node (ref "S13") (pin "2") (pinfunction "2_2") (pintype "passive"))
      (node (ref "TVS14") (pin "A") (pinfunction "1_A") (pintype "passive"))
      (node (ref "W14") (pin "2") (pinfunction "2_2") (pintype "passive"))
    )
    (net (code "71") (name "Net-(TVS15-1)") (class "Default")
      (node (ref "S15") (pin "1") (pinfunction "1_1") (pintype "passive"))
      (node (ref "TVS15") (pin "A") (pinfunction "1_A") (pintype "passive"))
      (node (ref "W15") (pin "2") (pinfunction "2_2") (pintype "passive"))
    )
    (net (code "72") (name "Net-(TVS16-1)") (class "Default")
      (node (ref "S15") (pin "2") (pinfunction "2_2") (pintype "passive"))
      (node (ref "TVS16") (pin "A") (pinfunction "1_A") (pintype "passive"))
      (node (ref "W16") (pin "2") (pinfunction "2_2") (pintype "passive"))
    )
    (net (code "73") (name "VCC") (class "Default")
      (node (ref "C1") (pin "1") (pinfunction "1_1") (pintype "passive"))
      (node (ref "C2") (pin "1") (pinfunction "1_1") (pintype "passive"))
      (node (ref "EXTIN") (pin "2") (pinfunction "2_2") (pintype "passive"))
      (node (ref "EXTOUT") (pin "8") (pinfunction "8_8") (pintype "passive"))
      (node (ref "IC1") (pin "10") (pinfunction "SCL_10") (pintype "input"))
      (node (ref "IC1") (pin "16") (pinfunction "VCC_16") (pintype "power_in"))
      (node (ref "IC2") (pin "10") (pinfunction "SCL_10") (pintype "input"))
      (node (ref "IC2") (pin "16") (pinfunction "VCC_16") (pintype "power_in"))
    )
  )
)
